# programming.net
KiCad netlist of a schematic drawn in Altium Designer
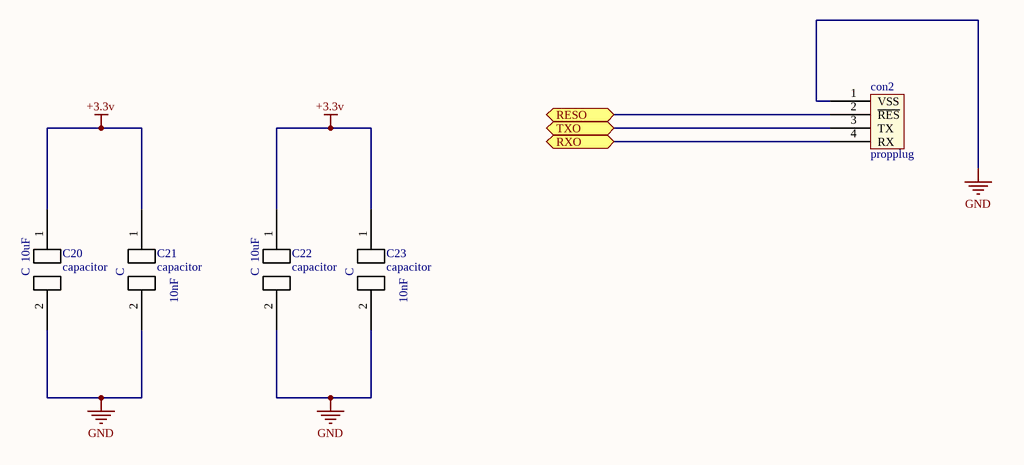
[diagram p0: programming.SchDoc]

(export (version "E")
  (design (tool "Eeschema 10.0.6"))
  (components
    (comp (ref "C20")
      (value "capacitor")
      (footprint "0603")
      (fields (field (name "ALTIUM_UNNAMED_1") "10uF"))
      (libsource (lib "pasives") (part "capacitor"))
    )
    (comp (ref "C21")
      (value "capacitor")
      (footprint "0603")
      (fields (field (name "ALTIUM_UNNAMED_1") "10nF"))
      (libsource (lib "pasives") (part "capacitor"))
    )
    (comp (ref "C22")
      (value "capacitor")
      (footprint "0603")
      (fields (field (name "ALTIUM_UNNAMED_1") "10uF"))
      (libsource (lib "pasives") (part "capacitor"))
    )
    (comp (ref "C23")
      (value "capacitor")
      (footprint "0603")
      (fields (field (name "ALTIUM_UNNAMED_1") "10nF"))
      (libsource (lib "pasives") (part "capacitor"))
    )
    (comp (ref "con2") (value "propplug") (libsource (lib "conector's_and_TP") (part "propplug")))
  )
  (nets
    (net (code "1") (name "+3.3v") (class "Default")
      (node (ref "C20") (pin "1") (pinfunction "1_1") (pintype "passive"))
      (node (ref "C21") (pin "1") (pinfunction "1_1") (pintype "passive"))
      (node (ref "C22") (pin "1") (pinfunction "1_1") (pintype "passive"))
      (node (ref "C23") (pin "1") (pinfunction "1_1") (pintype "passive"))
    )
    (net (code "2") (name "/RESO") (class "Default")
      (node (ref "con2") (pin "2") (pinfunction "~{RES}_2") (pintype "passive"))
    )
    (net (code "3") (name "/RXO") (class "Default")
      (node (ref "con2") (pin "4") (pinfunction "RX_4") (pintype "passive"))
    )
    (net (code "4") (name "/TXO") (class "Default")
      (node (ref "con2") (pin "3") (pinfunction "TX_3") (pintype "passive"))
    )
    (net (code "5") (name "GND") (class "Default")
      (node (ref "C20") (pin "2") (pinfunction "2_2") (pintype "passive"))
      (node (ref "C21") (pin "2") (pinfunction "2_2") (pintype "passive"))
      (node (ref "C22") (pin "2") (pinfunction "2_2") (pintype "passive"))
      (node (ref "C23") (pin "2") (pinfunction "2_2") (pintype "passive"))
      (node (ref "con2") (pin "1") (pinfunction "VSS_1") (pintype "passive"))
    )
  )
)
